# Pikachu_Charger.net
KiCad netlist of a schematic drawn in Altium Designer
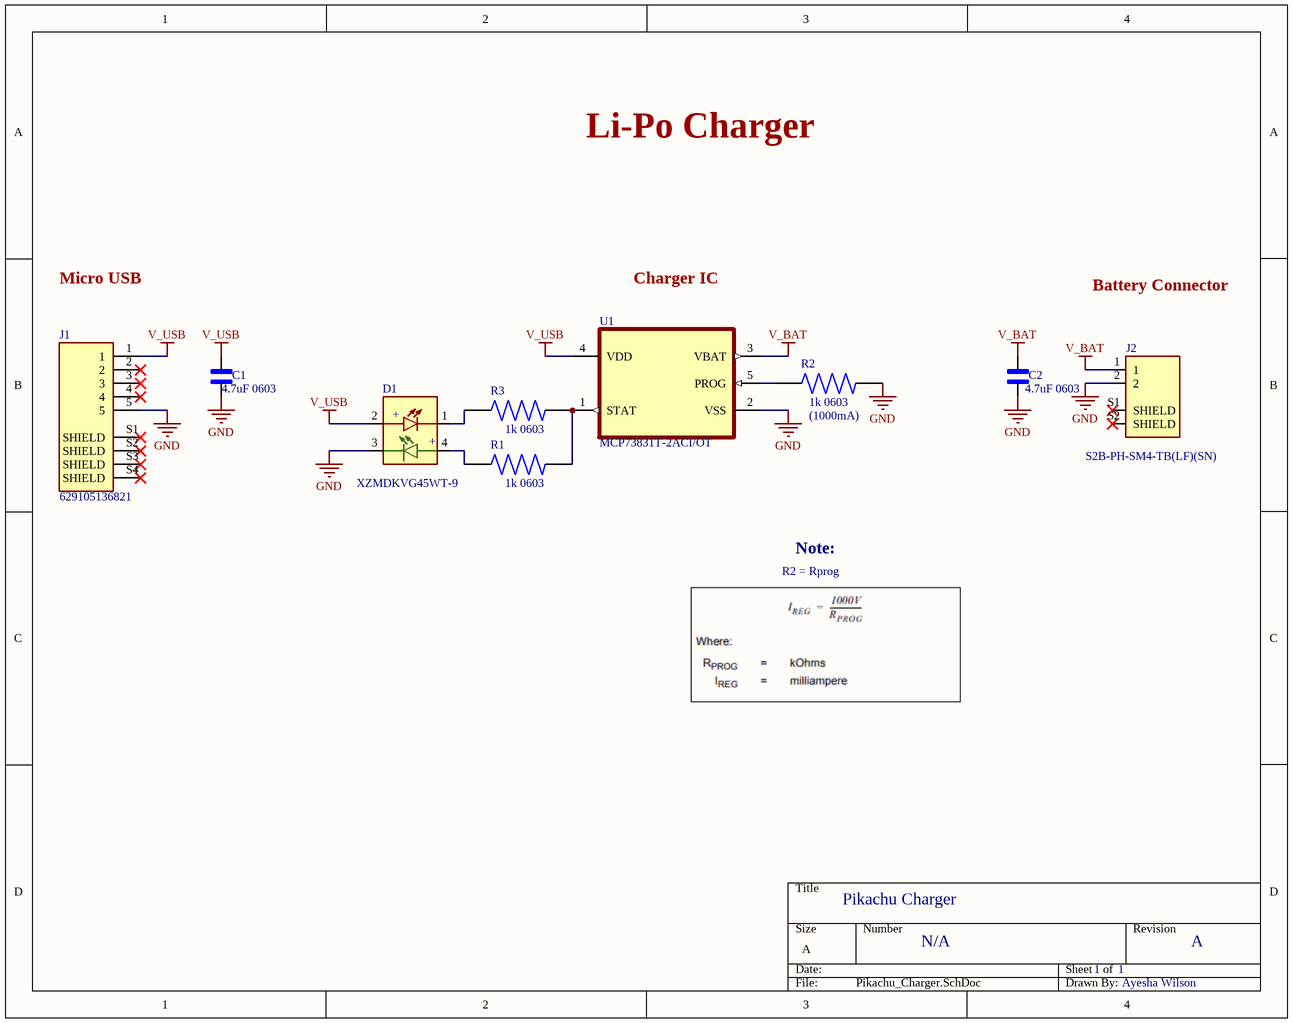
[diagram p0: Pikachu_Charger.SchDoc]

(export (version "E")
  (design (tool "Eeschema 10.0.6"))
  (components
    (comp (ref "C1")
      (value "4.7uF 0603")
      (footprint "CAPC1608X100N:CAPC1608X100N")
      (description "SMD Capacitor X5R(EIA) with Capacitance: 4.7uF Tol. 10%. Rated Voltage: 25Vdc")
      (fields (field (name "MF") "Murata Electronics") (field (name "MP") "GRT188R61E475KE13D"))
      (libsource (lib "GRM188R61E106KA73J") (part "GRM188R61E106KA73J"))
    )
    (comp (ref "C2")
      (value "4.7uF 0603")
      (footprint "CAPC1608X100N:CAPC1608X100N")
      (description "SMD Capacitor X5R(EIA) with Capacitance: 4.7uF Tol. 10%. Rated Voltage: 25Vdc")
      (fields (field (name "MF") "Murata Electronics") (field (name "MP") "GRT188R61E475KE13D"))
      (libsource (lib "GRM188R61E106KA73J") (part "GRM188R61E106KA73J"))
    )
    (comp (ref "D1")
      (value "XZMDKVG45WT-9")
      (footprint "XZMDKVG45WT-9")
      (fields (field (name "MF") "SunLED"))
      (libsource (lib "Pikachu_Charger") (part "XZMDKVG45WT-9"))
    )
    (comp (ref "J1")
      (value "629105136821")
      (footprint "SnapEDApcb:WE_629105136821")
      (description "USB - micro B USB 2.0 Receptacle Connector 5 Position Surface Mount, Right Angle")
      (fields (field (name "MF") "Wurth Electronics"))
      (libsource (lib "SnapEDAsch") (part "629105136821"))
    )
    (comp (ref "J2")
      (value "S2B-PH-SM4-TB(LF)(SN)")
      (footprint "JST_S2B-PH-SM4-TB(LF)(SN)")
      (description "Connector Header Surface Mount, Right Angle 2 position 0.079 (2.00mm)")
      (fields (field (name "MF") "JST Sales") (field (name "DIGI-KEY_PART_NUMBER") "455-1749-2-ND"))
      (libsource (lib "S2B-PH-SM4-TB(LF)(SN)") (part "S2B-PH-SM4-TB(LF)(SN)"))
    )
    (comp (ref "R1")
      (value "1k 0603")
      (footprint "RESC1508X55N:RESC1508X55N")
      (fields (field (name "MF") "Vishay") (field (name "MP") "MCT0603HC1001FP100"))
      (libsource (lib "MCT0603HC1001FP100") (part "MCT0603HC1001FP100"))
    )
    (comp (ref "R2")
      (value "1k 0603")
      (footprint "RESC1508X55N:RESC1508X55N")
      (fields (field (name "MF") "Vishay") (field (name "MP") "MCT0603HC1001FP100"))
      (libsource (lib "MCT0603HC1001FP100") (part "MCT0603HC1001FP100"))
    )
    (comp (ref "R3")
      (value "1k 0603")
      (footprint "RESC1508X55N:RESC1508X55N")
      (fields (field (name "MF") "Vishay") (field (name "MP") "MCT0603HC1001FP100"))
      (libsource (lib "MCT0603HC1001FP100") (part "MCT0603HC1001FP100"))
    )
    (comp (ref "U1")
      (value "MCP73831T-2ACI/OT")
      (footprint "SOT95P280X145-5N")
      (description "Charger IC Lithium Ion/Polymer SOT-23-5")
      (fields (field (name "MF") "Microchip"))
      (libsource (lib "MCP73831T-2ACI_OT") (part "MCP73831T-2ACI/OT"))
    )
  )
  (nets
    (net (code "1") (name "GND") (class "Default")
      (node (ref "C1") (pin "1") (pinfunction "1_1") (pintype "passive"))
      (node (ref "C2") (pin "1") (pinfunction "1_1") (pintype "passive"))
      (node (ref "D1") (pin "3") (pinfunction "V-_3") (pintype "passive"))
      (node (ref "J1") (pin "5") (pinfunction "5_5") (pintype "passive"))
      (node (ref "J2") (pin "2") (pinfunction "2_2") (pintype "passive"))
      (node (ref "R2") (pin "2") (pinfunction "2_2") (pintype "passive"))
      (node (ref "U1") (pin "2") (pinfunction "VSS_2") (pintype "power_in"))
    )
    (net (code "2") (name "Net-(D1-S-)") (class "Default")
      (node (ref "D1") (pin "1") (pinfunction "S-_1") (pintype "passive"))
      (node (ref "R3") (pin "1") (pinfunction "1_1") (pintype "passive"))
    )
    (net (code "3") (name "Net-(D1-V+)") (class "Default")
      (node (ref "D1") (pin "4") (pinfunction "V+_4") (pintype "passive"))
      (node (ref "R1") (pin "1") (pinfunction "1_1") (pintype "passive"))
    )
    (net (code "4") (name "Net-(U1-PROG)") (class "Default")
      (node (ref "R2") (pin "1") (pinfunction "1_1") (pintype "passive"))
      (node (ref "U1") (pin "5") (pinfunction "PROG_5") (pintype "input"))
    )
    (net (code "5") (name "Net-(U1-STAT)") (class "Default")
      (node (ref "R1") (pin "2") (pinfunction "2_2") (pintype "passive"))
      (node (ref "R3") (pin "2") (pinfunction "2_2") (pintype "passive"))
      (node (ref "U1") (pin "1") (pinfunction "STAT_1") (pintype "output"))
    )
    (net (code "6") (name "V_BAT") (class "Default")
      (node (ref "C2") (pin "2") (pinfunction "2_2") (pintype "passive"))
      (node (ref "J2") (pin "1") (pinfunction "1_1") (pintype "passive"))
      (node (ref "U1") (pin "3") (pinfunction "VBAT_3") (pintype "output"))
    )
    (net (code "7") (name "V_USB") (class "Default")
      (node (ref "C1") (pin "2") (pinfunction "2_2") (pintype "passive"))
      (node (ref "D1") (pin "2") (pinfunction "S+_2") (pintype "passive"))
      (node (ref "J1") (pin "1") (pinfunction "1_1") (pintype "passive"))
      (node (ref "U1") (pin "4") (pinfunction "VDD_4") (pintype "power_in"))
    )
    (net (code "8") (name "unconnected-(J1-Pad2)") (class "Default")
      (node (ref "J1") (pin "2") (pinfunction "2_2") (pintype "passive+no_connect"))
    )
    (net (code "9") (name "unconnected-(J1-Pad3)") (class "Default")
      (node (ref "J1") (pin "3") (pinfunction "3_3") (pintype "passive+no_connect"))
    )
    (net (code "10") (name "unconnected-(J1-Pad4)") (class "Default")
      (node (ref "J1") (pin "4") (pinfunction "4_4") (pintype "passive+no_connect"))
    )
    (net (code "11") (name "unconnected-(J1-SHIELD-PadS1)") (class "Default")
      (node (ref "J1") (pin "S1") (pinfunction "SHIELD_S1") (pintype "passive+no_connect"))
    )
    (net (code "12") (name "unconnected-(J1-SHIELD-PadS2)") (class "Default")
      (node (ref "J1") (pin "S2") (pinfunction "SHIELD_S2") (pintype "passive+no_connect"))
    )
    (net (code "13") (name "unconnected-(J1-SHIELD-PadS3)") (class "Default")
      (node (ref "J1") (pin "S3") (pinfunction "SHIELD_S3") (pintype "passive+no_connect"))
    )
    (net (code "14") (name "unconnected-(J1-SHIELD-PadS4)") (class "Default")
      (node (ref "J1") (pin "S4") (pinfunction "SHIELD_S4") (pintype "passive+no_connect"))
    )
    (net (code "15") (name "unconnected-(J2-SHIELD-PadS1)") (class "Default")
      (node (ref "J2") (pin "S1") (pinfunction "SHIELD_S1") (pintype "passive+no_connect"))
    )
    (net (code "16") (name "unconnected-(J2-SHIELD-PadS2)") (class "Default")
      (node (ref "J2") (pin "S2") (pinfunction "SHIELD_S2") (pintype "passive+no_connect"))
    )
  )
)
